# DSO_Trig.net
KiCad netlist of a schematic drawn in Altium Designer
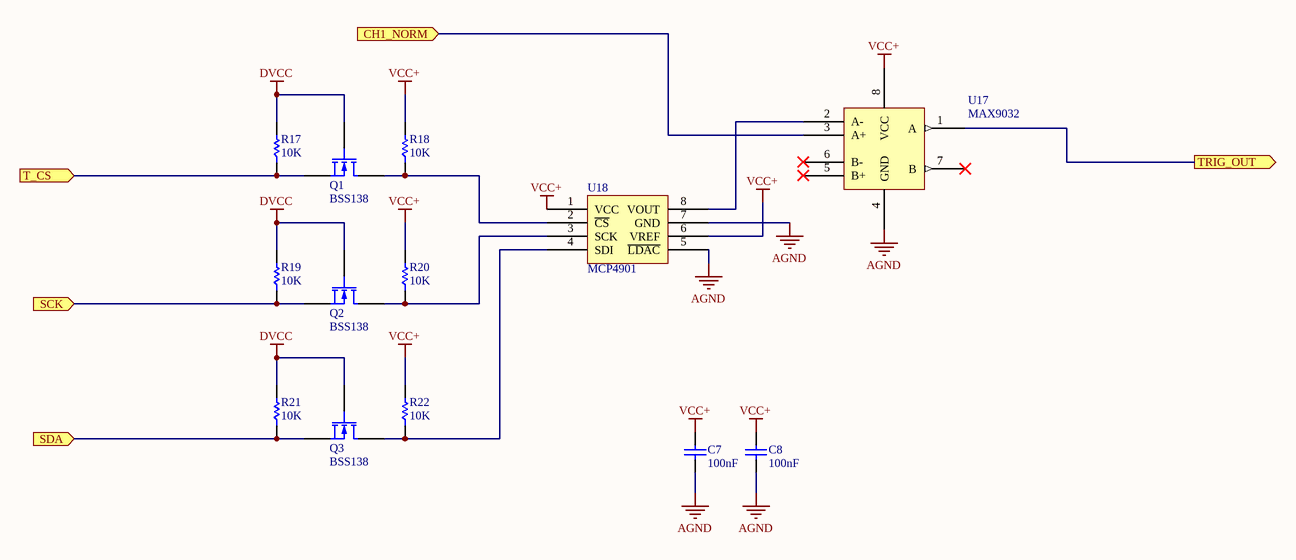
[diagram p0: DSO_Trig.SchDoc]

(export (version "E")
  (design (tool "Eeschema 10.0.6"))
  (components
    (comp (ref "C7")
      (value "100nF")
      (footprint "0805C")
      (description "Capacitor")
      (fields (field (name "REVIEWED BY") "RM - 2018/08/05"))
      (libsource (lib "DSO") (part "C"))
    )
    (comp (ref "C8")
      (value "100nF")
      (footprint "0805C")
      (description "Capacitor")
      (fields (field (name "REVIEWED BY") "RM - 2018/08/05"))
      (libsource (lib "DSO") (part "C"))
    )
    (comp (ref "Q1")
      (value "BSS138")
      (footprint "SOT23")
      (description "N-Channel MOSFET")
      (fields (field (name "PUBLISHER") "Altium Limited"))
      (libsource (lib "DSO") (part "MOSFET-N"))
    )
    (comp (ref "Q2")
      (value "BSS138")
      (footprint "SOT23")
      (description "N-Channel MOSFET")
      (fields (field (name "PUBLISHER") "Altium Limited"))
      (libsource (lib "DSO") (part "MOSFET-N"))
    )
    (comp (ref "Q3")
      (value "BSS138")
      (footprint "SOT23")
      (description "N-Channel MOSFET")
      (fields (field (name "PUBLISHER") "Altium Limited"))
      (libsource (lib "DSO") (part "MOSFET-N"))
    )
    (comp (ref "R17")
      (value "10K")
      (footprint "0805")
      (description "Resistor")
      (fields (field (name "REVIEWED BY") "RM - 2018/08/05"))
      (libsource (lib "DSO") (part "R"))
    )
    (comp (ref "R18")
      (value "10K")
      (footprint "0805")
      (description "Resistor")
      (fields (field (name "REVIEWED BY") "RM - 2018/08/05"))
      (libsource (lib "DSO") (part "R"))
    )
    (comp (ref "R19")
      (value "10K")
      (footprint "0805")
      (description "Resistor")
      (fields (field (name "REVIEWED BY") "RM - 2018/08/05"))
      (libsource (lib "DSO") (part "R"))
    )
    (comp (ref "R20")
      (value "10K")
      (footprint "0805")
      (description "Resistor")
      (fields (field (name "REVIEWED BY") "RM - 2018/08/05"))
      (libsource (lib "DSO") (part "R"))
    )
    (comp (ref "R21")
      (value "10K")
      (footprint "0805")
      (description "Resistor")
      (fields (field (name "REVIEWED BY") "RM - 2018/08/05"))
      (libsource (lib "DSO") (part "R"))
    )
    (comp (ref "R22")
      (value "10K")
      (footprint "0805")
      (description "Resistor")
      (fields (field (name "REVIEWED BY") "RM - 2018/08/05"))
      (libsource (lib "DSO") (part "R"))
    )
    (comp (ref "U17")
      (value "MAX9032")
      (footprint "SOIC-8")
      (description "Dual Comparator")
      (fields (field (name "REVIEWED BY") "RM - 2018/08/05"))
      (libsource (lib "DSO") (part "MAX9032"))
    )
    (comp (ref "U18")
      (value "MCP4901")
      (footprint "SOIC-8")
      (description "DAC 8bit SPI")
      (fields (field (name "REVIEWED BY") "RM - 2018/08/05"))
      (libsource (lib "DSO") (part "MCP4901"))
    )
  )
  (nets
    (net (code "1") (name "/CH1_NORM") (class "Default")
      (node (ref "U17") (pin "3") (pinfunction "A+_3") (pintype "passive"))
    )
    (net (code "2") (name "/SCK") (class "Default")
      (node (ref "Q2") (pin "2") (pinfunction "2_2") (pintype "passive"))
      (node (ref "R19") (pin "1") (pintype "passive"))
    )
    (net (code "3") (name "/SDA") (class "Default")
      (node (ref "Q3") (pin "2") (pinfunction "2_2") (pintype "passive"))
      (node (ref "R21") (pin "1") (pintype "passive"))
    )
    (net (code "4") (name "/TRIG_OUT") (class "Default")
      (node (ref "U17") (pin "1") (pinfunction "A_1") (pintype "output"))
    )
    (net (code "5") (name "/T_CS") (class "Default")
      (node (ref "Q1") (pin "2") (pinfunction "2_2") (pintype "passive"))
      (node (ref "R17") (pin "1") (pintype "passive"))
    )
    (net (code "6") (name "AGND") (class "Default")
      (node (ref "C7") (pin "2") (pinfunction "2_2") (pintype "passive"))
      (node (ref "C8") (pin "2") (pinfunction "2_2") (pintype "passive"))
      (node (ref "U17") (pin "4") (pinfunction "GND_4") (pintype "passive"))
      (node (ref "U18") (pin "5") (pinfunction "~{LDAC}_5") (pintype "passive"))
      (node (ref "U18") (pin "7") (pinfunction "GND_7") (pintype "passive"))
    )
    (net (code "7") (name "DVCC") (class "Default")
      (node (ref "Q1") (pin "1") (pinfunction "1_1") (pintype "passive"))
      (node (ref "Q2") (pin "1") (pinfunction "1_1") (pintype "passive"))
      (node (ref "Q3") (pin "1") (pinfunction "1_1") (pintype "passive"))
      (node (ref "R17") (pin "2") (pintype "passive"))
      (node (ref "R19") (pin "2") (pintype "passive"))
      (node (ref "R21") (pin "2") (pintype "passive"))
    )
    (net (code "8") (name "Net-(U17-A-)") (class "Default")
      (node (ref "U17") (pin "2") (pinfunction "A-_2") (pintype "passive"))
      (node (ref "U18") (pin "8") (pinfunction "VOUT_8") (pintype "passive"))
    )
    (net (code "9") (name "Net-(U18-SCK)") (class "Default")
      (node (ref "Q2") (pin "3") (pinfunction "3_3") (pintype "passive"))
      (node (ref "R20") (pin "1") (pintype "passive"))
      (node (ref "U18") (pin "3") (pinfunction "SCK_3") (pintype "passive"))
    )
    (net (code "10") (name "Net-(U18-SDI)") (class "Default")
      (node (ref "Q3") (pin "3") (pinfunction "3_3") (pintype "passive"))
      (node (ref "R22") (pin "1") (pintype "passive"))
      (node (ref "U18") (pin "4") (pinfunction "SDI_4") (pintype "passive"))
    )
    (net (code "11") (name "Net-(U18-~{CS})") (class "Default")
      (node (ref "Q1") (pin "3") (pinfunction "3_3") (pintype "passive"))
      (node (ref "R18") (pin "1") (pintype "passive"))
      (node (ref "U18") (pin "2") (pinfunction "~{CS}_2") (pintype "passive"))
    )
    (net (code "12") (name "VCC+") (class "Default")
      (node (ref "C7") (pin "1") (pinfunction "1_1") (pintype "passive"))
      (node (ref "C8") (pin "1") (pinfunction "1_1") (pintype "passive"))
      (node (ref "R18") (pin "2") (pintype "passive"))
      (node (ref "R20") (pin "2") (pintype "passive"))
      (node (ref "R22") (pin "2") (pintype "passive"))
      (node (ref "U17") (pin "8") (pinfunction "VCC_8") (pintype "passive"))
      (node (ref "U18") (pin "1") (pinfunction "VCC_1") (pintype "passive"))
      (node (ref "U18") (pin "6") (pinfunction "VREF_6") (pintype "passive"))
    )
    (net (code "13") (name "unconnected-(U17-B+-Pad5)") (class "Default")
      (node (ref "U17") (pin "5") (pinfunction "B+_5") (pintype "passive+no_connect"))
    )
    (net (code "14") (name "unconnected-(U17-B--Pad6)") (class "Default")
      (node (ref "U17") (pin "6") (pinfunction "B-_6") (pintype "passive+no_connect"))
    )
    (net (code "15") (name "unconnected-(U17-B-Pad7)") (class "Default")
      (node (ref "U17") (pin "7") (pinfunction "B_7") (pintype "output+no_connect"))
    )
  )
)
